# LED_card_GC_REV2.net
KiCad netlist of a schematic drawn in EAGLE
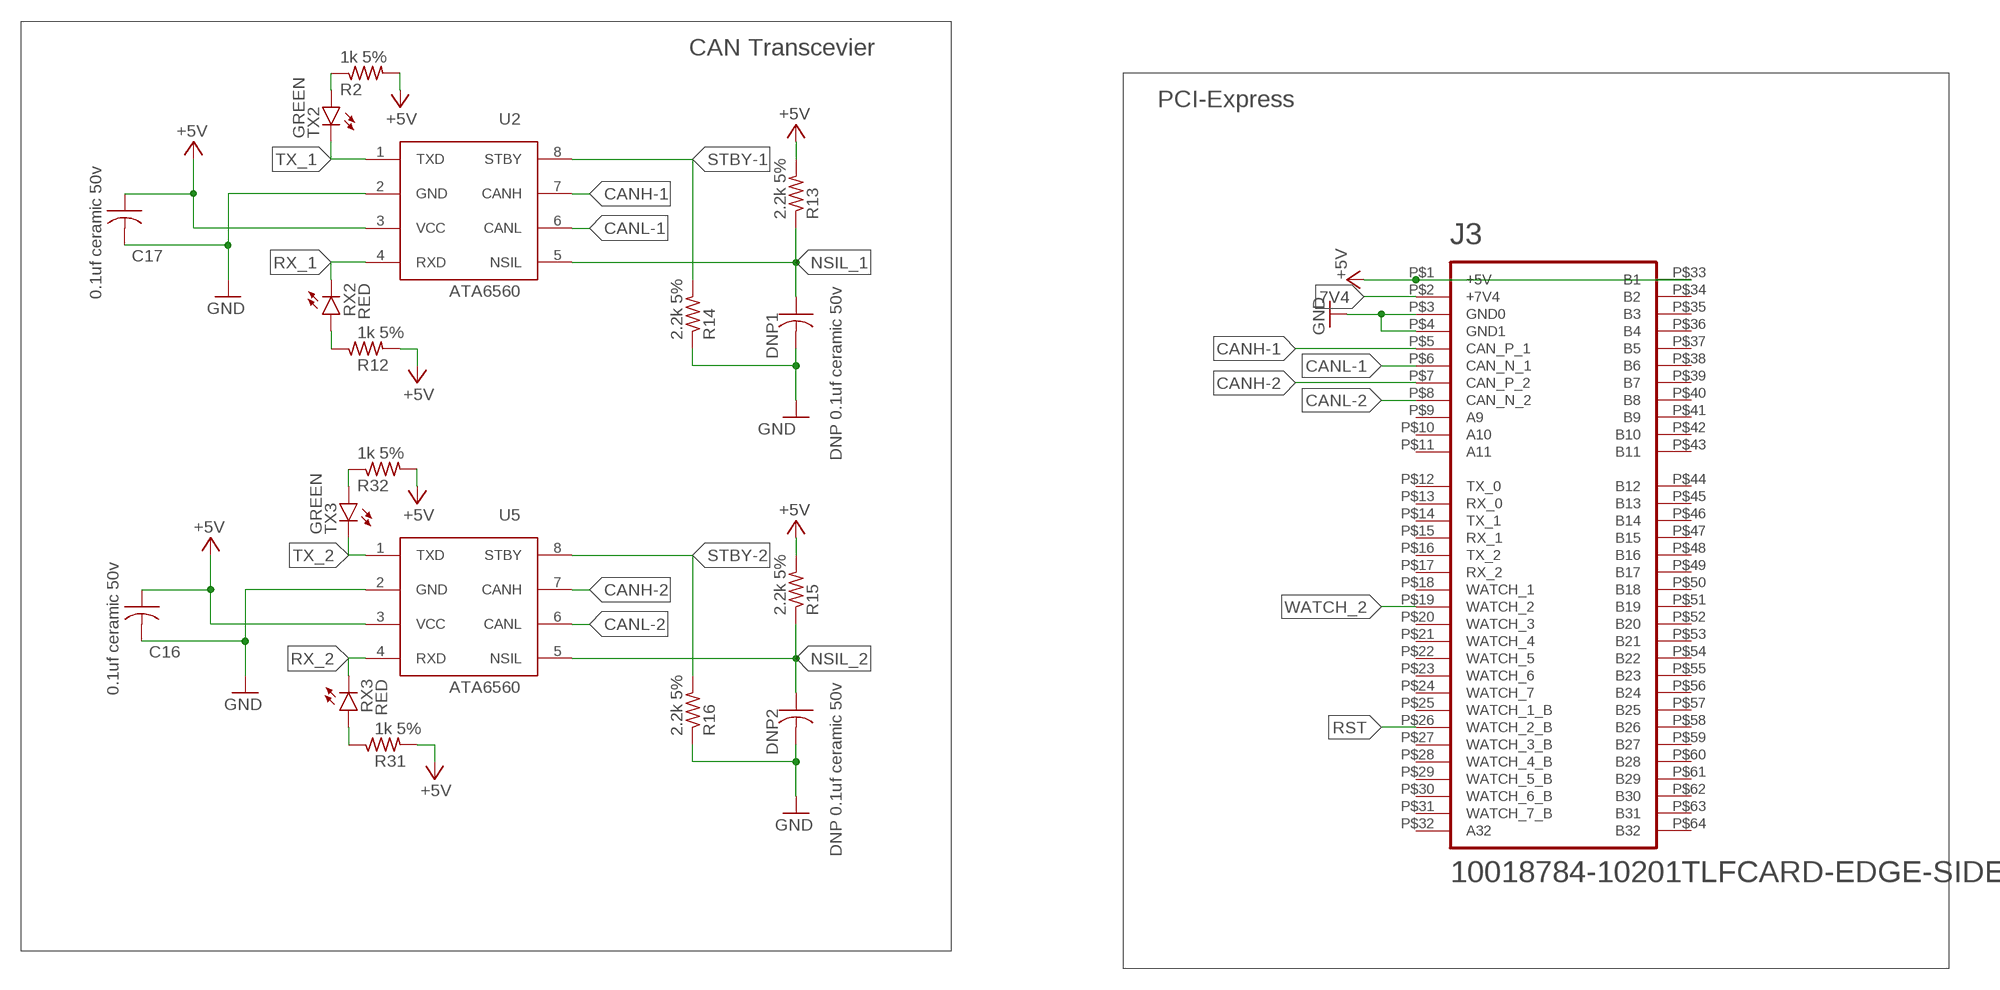
[diagram p0: schematic, sheet 1, part 1 of 3]
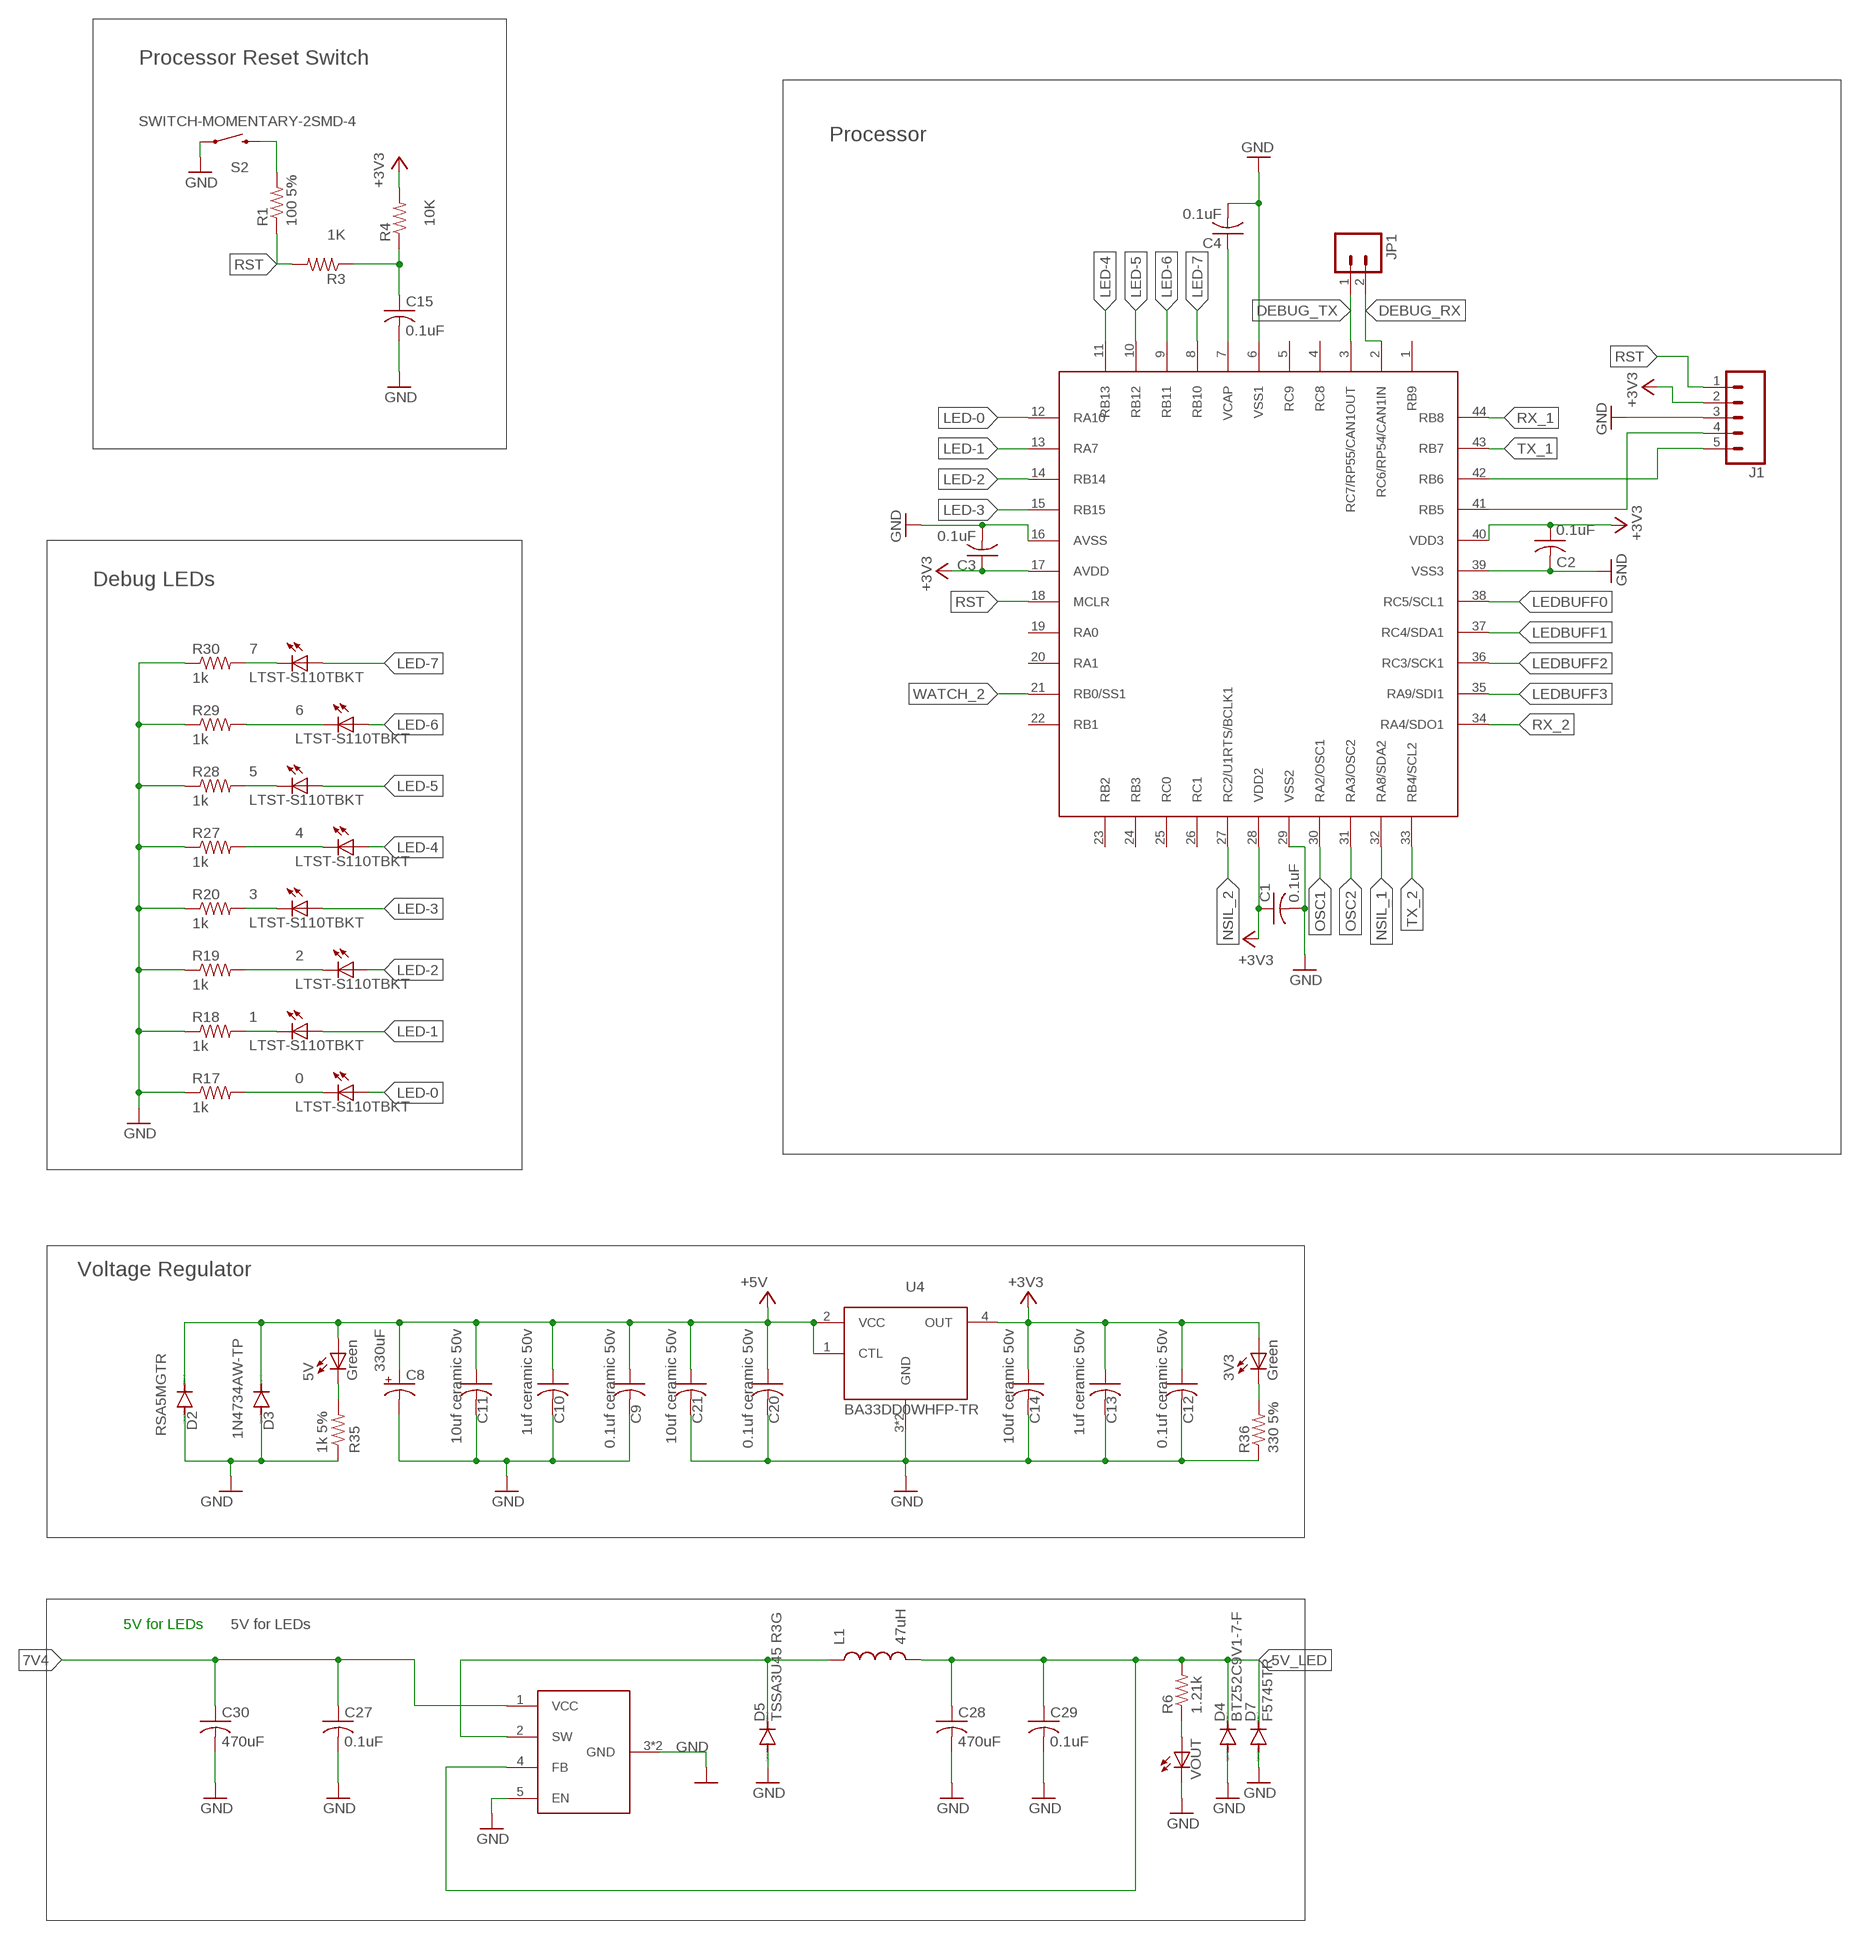
[diagram p1: schematic, sheet 1, part 2 of 3]
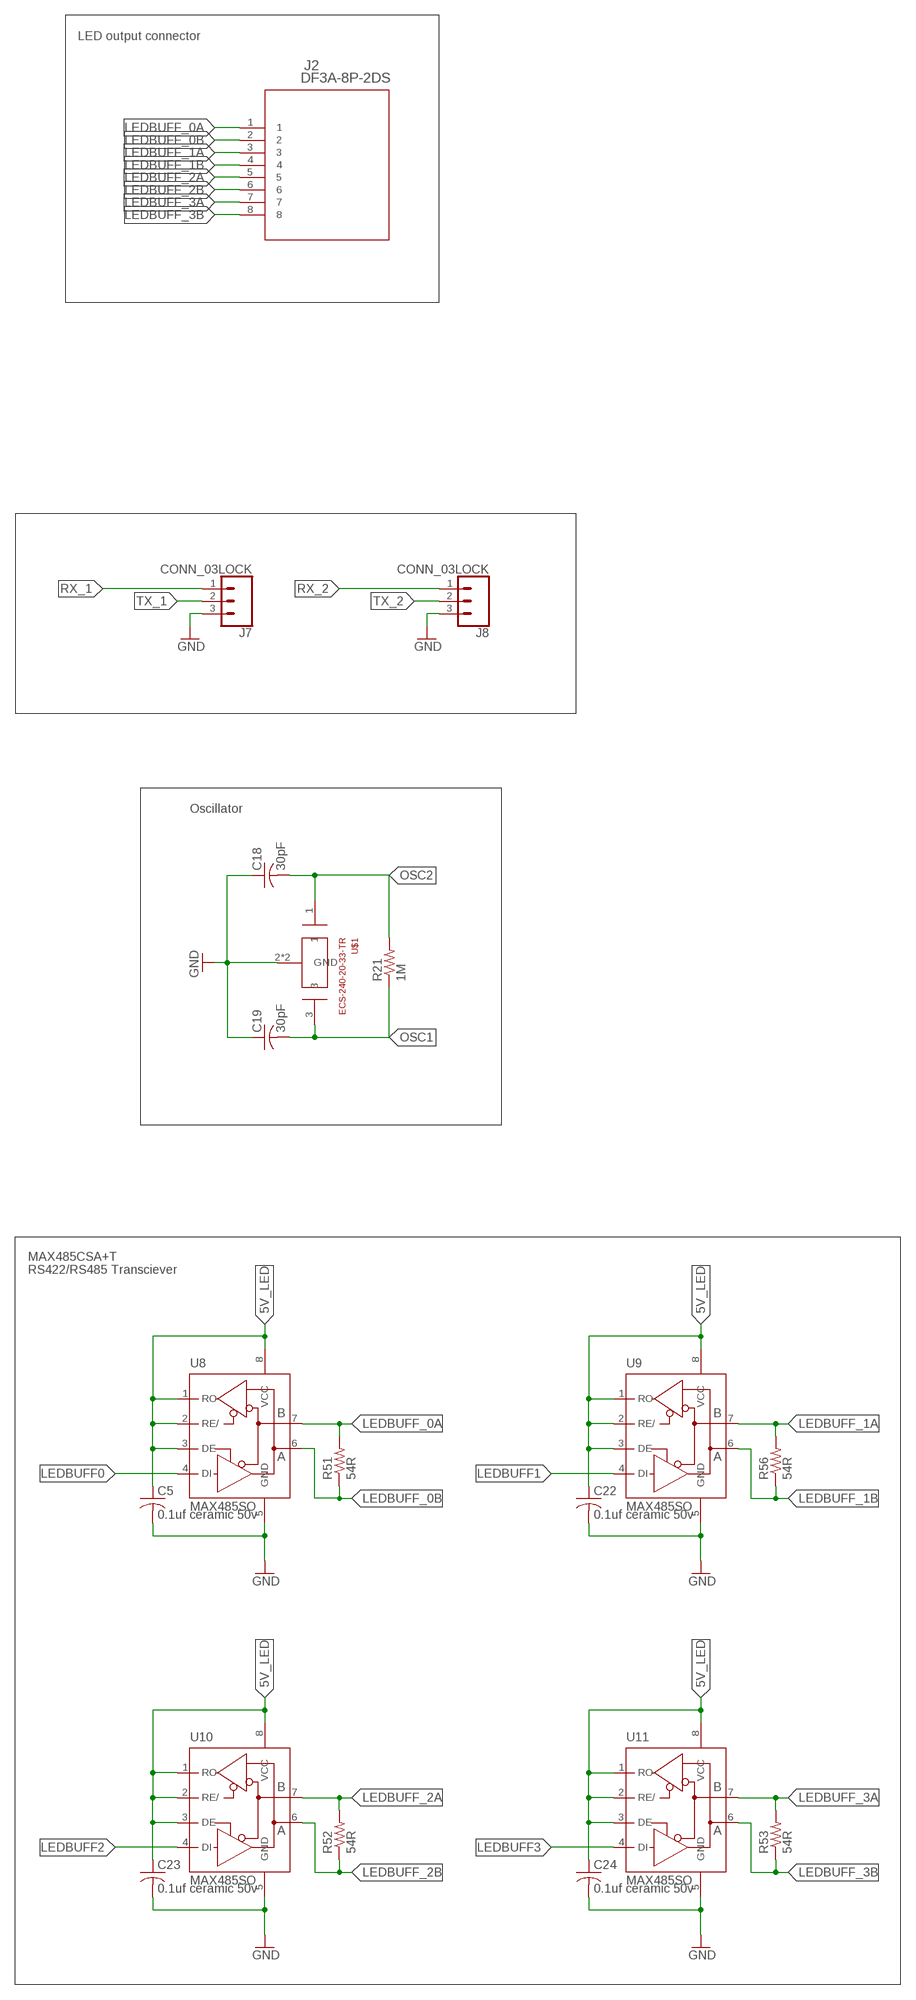
[diagram p2: schematic, sheet 1, part 3 of 3]

(export (version "E")
  (design (tool "Eeschema 10.0.6"))
  (components
    (comp (ref "0")
      (value "LTST-S110TBKT")
      (footprint "eagle-import:LED-90")
      (libsource (lib "eagle-import") (part "LTST-S110TBKT"))
    )
    (comp (ref "1")
      (value "LTST-S110TBKT")
      (footprint "eagle-import:LED-90")
      (libsource (lib "eagle-import") (part "LTST-S110TBKT"))
    )
    (comp (ref "2")
      (value "LTST-S110TBKT")
      (footprint "eagle-import:LED-90")
      (libsource (lib "eagle-import") (part "LTST-S110TBKT"))
    )
    (comp (ref "3")
      (value "LTST-S110TBKT")
      (footprint "eagle-import:LED-90")
      (libsource (lib "eagle-import") (part "LTST-S110TBKT"))
    )
    (comp (ref "3V3")
      (value "Green")
      (footprint "eagle-import:LED-90")
      (libsource (lib "eagle-import") (part "LTST-S110TBKT"))
    )
    (comp (ref "4")
      (value "LTST-S110TBKT")
      (footprint "eagle-import:LED-90")
      (libsource (lib "eagle-import") (part "LTST-S110TBKT"))
    )
    (comp (ref "5")
      (value "LTST-S110TBKT")
      (footprint "eagle-import:LED-90")
      (libsource (lib "eagle-import") (part "LTST-S110TBKT"))
    )
    (comp (ref "5V")
      (value "Green")
      (footprint "eagle-import:LED-90")
      (libsource (lib "eagle-import") (part "LTST-S110TBKT"))
    )
    (comp (ref "6")
      (value "LTST-S110TBKT")
      (footprint "eagle-import:LED-90")
      (libsource (lib "eagle-import") (part "LTST-S110TBKT"))
    )
    (comp (ref "7")
      (value "LTST-S110TBKT")
      (footprint "eagle-import:LED-90")
      (libsource (lib "eagle-import") (part "LTST-S110TBKT"))
    )
    (comp (ref "C1")
      (value "0.1uF")
      (footprint "eagle-import:C0805")
      (libsource (lib "eagle-import") (part "C-US_0805C0805"))
    )
    (comp (ref "C2")
      (value "0.1uF")
      (footprint "eagle-import:C0805")
      (libsource (lib "eagle-import") (part "C-US_0805C0805"))
    )
    (comp (ref "C3")
      (value "0.1uF")
      (footprint "eagle-import:C0805")
      (libsource (lib "eagle-import") (part "C-US_0805C0805"))
    )
    (comp (ref "C4")
      (value "0.1uF")
      (footprint "eagle-import:C0805")
      (libsource (lib "eagle-import") (part "C-US_0805C0805"))
    )
    (comp (ref "C5")
      (value "0.1uf ceramic 50v")
      (footprint "eagle-import:C0805")
      (libsource (lib "eagle-import") (part "rcl_C-USC0805"))
    )
    (comp (ref "C8")
      (value "330uF")
      (footprint "eagle-import:140CLH-1014")
      (libsource (lib "eagle-import") (part "CPOL-US140CLH-1014"))
    )
    (comp (ref "C9")
      (value "0.1uf ceramic 50v")
      (footprint "eagle-import:C0805")
      (libsource (lib "eagle-import") (part "C-US_0805C0805"))
    )
    (comp (ref "C10")
      (value "1uf ceramic 50v")
      (footprint "eagle-import:C0805")
      (libsource (lib "eagle-import") (part "C-US_0805C0805"))
    )
    (comp (ref "C11")
      (value "10uf ceramic 50v")
      (footprint "eagle-import:C0805")
      (libsource (lib "eagle-import") (part "C-US_0805C0805"))
    )
    (comp (ref "C12")
      (value "0.1uf ceramic 50v")
      (footprint "eagle-import:C0805")
      (libsource (lib "eagle-import") (part "C-US_0805C0805"))
    )
    (comp (ref "C13")
      (value "1uf ceramic 50v")
      (footprint "eagle-import:C0805")
      (libsource (lib "eagle-import") (part "C-US_0805C0805"))
    )
    (comp (ref "C14")
      (value "10uf ceramic 50v")
      (footprint "eagle-import:C0805")
      (libsource (lib "eagle-import") (part "C-US_0805C0805"))
    )
    (comp (ref "C15")
      (value "0.1uF")
      (footprint "eagle-import:C0805")
      (libsource (lib "eagle-import") (part "C-US_0805C0805"))
    )
    (comp (ref "C16")
      (value "0.1uf ceramic 50v")
      (footprint "eagle-import:C0805")
      (libsource (lib "eagle-import") (part "C-US_0805C0805"))
    )
    (comp (ref "C17")
      (value "0.1uf ceramic 50v")
      (footprint "eagle-import:C0805")
      (libsource (lib "eagle-import") (part "C-US_0805C0805"))
    )
    (comp (ref "C18")
      (value "30pF")
      (footprint "eagle-import:C0805")
      (libsource (lib "eagle-import") (part "C-US_0805C0805"))
    )
    (comp (ref "C19")
      (value "30pF")
      (footprint "eagle-import:C0805")
      (libsource (lib "eagle-import") (part "C-US_0805C0805"))
    )
    (comp (ref "C20")
      (value "0.1uf ceramic 50v")
      (footprint "eagle-import:C0805")
      (libsource (lib "eagle-import") (part "C-US_0805C0805"))
    )
    (comp (ref "C21")
      (value "10uf ceramic 50v")
      (footprint "eagle-import:C0805")
      (libsource (lib "eagle-import") (part "C-US_0805C0805"))
    )
    (comp (ref "C22")
      (value "0.1uf ceramic 50v")
      (footprint "eagle-import:C0805")
      (libsource (lib "eagle-import") (part "rcl_C-USC0805"))
    )
    (comp (ref "C23")
      (value "0.1uf ceramic 50v")
      (footprint "eagle-import:C0805")
      (libsource (lib "eagle-import") (part "rcl_C-USC0805"))
    )
    (comp (ref "C24")
      (value "0.1uf ceramic 50v")
      (footprint "eagle-import:C0805")
      (libsource (lib "eagle-import") (part "rcl_C-USC0805"))
    )
    (comp (ref "C27")
      (value "0.1uF")
      (footprint "eagle-import:C1825")
      (libsource (lib "eagle-import") (part "C-USC1825"))
    )
    (comp (ref "C28")
      (value "470uF")
      (footprint "eagle-import:C1825")
      (libsource (lib "eagle-import") (part "C-USC1825"))
    )
    (comp (ref "C29")
      (value "0.1uF")
      (footprint "eagle-import:C1825")
      (libsource (lib "eagle-import") (part "C-USC1825"))
    )
    (comp (ref "C30")
      (value "470uF")
      (footprint "eagle-import:C1825")
      (libsource (lib "eagle-import") (part "C-USC1825"))
    )
    (comp (ref "D2")
      (value "RSA5MGTR")
      (footprint "eagle-import:SOD123")
      (libsource (lib "eagle-import") (part "DIODE-SOD123"))
    )
    (comp (ref "D3")
      (value "1N4734AW-TP")
      (footprint "eagle-import:SOD123")
      (fields (field (name "SPICEPREFIX") "D"))
      (libsource (lib "eagle-import") (part "DIODE-SOD123"))
    )
    (comp (ref "D4")
      (value "BTZ52C9V1-7-F")
      (footprint "eagle-import:SOD123")
      (libsource (lib "eagle-import") (part "DIODE-SOD123"))
    )
    (comp (ref "D5")
      (value "TSSA3U45 R3G")
      (footprint "eagle-import:DO214AC")
      (libsource (lib "eagle-import") (part "DIODE-DO214AC"))
    )
    (comp (ref "D7")
      (value "F5745TR")
      (footprint "eagle-import:SOD123")
      (libsource (lib "eagle-import") (part "DIODE-SOD123"))
    )
    (comp (ref "DNP1")
      (value "DNP 0.1uf ceramic 50v")
      (footprint "eagle-import:C0805")
      (libsource (lib "eagle-import") (part "C-US_0805C0805"))
    )
    (comp (ref "DNP2")
      (value "DNP 0.1uf ceramic 50v")
      (footprint "eagle-import:C0805")
      (libsource (lib "eagle-import") (part "C-US_0805C0805"))
    )
    (comp (ref "J1")
      (value "CONN_05LOCK")
      (footprint "eagle-import:1X05_LOCK")
      (libsource (lib "eagle-import") (part "CONN_05LOCK"))
    )
    (comp (ref "J2")
      (value "DF3A-8P-2DS")
      (footprint "eagle-import:CON8_1X8_R_DF3")
      (libsource (lib "eagle-import") (part "DF3A-8P-2DS"))
    )
    (comp (ref "J3")
      (value "10018784-10201TLFCARD-EDGE-SIDE")
      (footprint "eagle-import:CARDEDGE_SIDE")
      (libsource (lib "eagle-import") (part "10018784-10201TLFCARD-EDGE-SIDE"))
    )
    (comp (ref "J7")
      (value "CONN_03LOCK")
      (footprint "eagle-import:1X03_LOCK")
      (libsource (lib "eagle-import") (part "CONN_03LOCK"))
    )
    (comp (ref "J8")
      (value "CONN_03LOCK")
      (footprint "eagle-import:1X03_LOCK")
      (libsource (lib "eagle-import") (part "CONN_03LOCK"))
    )
    (comp (ref "JP1")
      (value "CONN_02PTH")
      (footprint "eagle-import:1X02")
      (libsource (lib "eagle-import") (part "CONN_02PTH"))
    )
    (comp (ref "L1")
      (value "47uH")
      (footprint "eagle-import:0805")
      (libsource (lib "eagle-import") (part "INDUCTOR1"))
    )
    (comp (ref "R1")
      (value "100 5%")
      (footprint "eagle-import:R0805")
      (libsource (lib "eagle-import") (part "R-US_0805R0805"))
    )
    (comp (ref "R2")
      (value "1k 5%")
      (footprint "eagle-import:R0805")
      (libsource (lib "eagle-import") (part "R-US_0805R0805"))
    )
    (comp (ref "R3")
      (value "1K")
      (footprint "eagle-import:R0805")
      (libsource (lib "eagle-import") (part "R-US_0805R0805"))
    )
    (comp (ref "R4")
      (value "10K")
      (footprint "eagle-import:R0805")
      (libsource (lib "eagle-import") (part "R-US_0805R0805"))
    )
    (comp (ref "R6")
      (value "1.21k")
      (footprint "eagle-import:R0805")
      (libsource (lib "eagle-import") (part "R-US_R0805"))
    )
    (comp (ref "R12")
      (value "1k 5%")
      (footprint "eagle-import:R0805")
      (libsource (lib "eagle-import") (part "R-US_0805R0805"))
    )
    (comp (ref "R13")
      (value "2.2k 5%")
      (footprint "eagle-import:R0805")
      (libsource (lib "eagle-import") (part "R-US_0805R0805"))
    )
    (comp (ref "R14")
      (value "2.2k 5%")
      (footprint "eagle-import:R0805")
      (libsource (lib "eagle-import") (part "R-US_0805R0805"))
    )
    (comp (ref "R15")
      (value "2.2k 5%")
      (footprint "eagle-import:R0805")
      (libsource (lib "eagle-import") (part "R-US_0805R0805"))
    )
    (comp (ref "R16")
      (value "2.2k 5%")
      (footprint "eagle-import:R0805")
      (libsource (lib "eagle-import") (part "R-US_0805R0805"))
    )
    (comp (ref "R17")
      (value "1k")
      (footprint "eagle-import:R0805")
      (libsource (lib "eagle-import") (part "R-US_0805R0805"))
    )
    (comp (ref "R18")
      (value "1k")
      (footprint "eagle-import:R0805")
      (libsource (lib "eagle-import") (part "R-US_0805R0805"))
    )
    (comp (ref "R19")
      (value "1k")
      (footprint "eagle-import:R0805")
      (libsource (lib "eagle-import") (part "R-US_0805R0805"))
    )
    (comp (ref "R20")
      (value "1k")
      (footprint "eagle-import:R0805")
      (libsource (lib "eagle-import") (part "R-US_0805R0805"))
    )
    (comp (ref "R21")
      (value "1M")
      (footprint "eagle-import:R0805")
      (libsource (lib "eagle-import") (part "R-US_0805R0805"))
    )
    (comp (ref "R27")
      (value "1k")
      (footprint "eagle-import:R0805")
      (libsource (lib "eagle-import") (part "R-US_0805R0805"))
    )
    (comp (ref "R28")
      (value "1k")
      (footprint "eagle-import:R0805")
      (libsource (lib "eagle-import") (part "R-US_0805R0805"))
    )
    (comp (ref "R29")
      (value "1k")
      (footprint "eagle-import:R0805")
      (libsource (lib "eagle-import") (part "R-US_0805R0805"))
    )
    (comp (ref "R30")
      (value "1k")
      (footprint "eagle-import:R0805")
      (libsource (lib "eagle-import") (part "R-US_0805R0805"))
    )
    (comp (ref "R31")
      (value "1k 5%")
      (footprint "eagle-import:R0805")
      (libsource (lib "eagle-import") (part "R-US_0805R0805"))
    )
    (comp (ref "R32")
      (value "1k 5%")
      (footprint "eagle-import:R0805")
      (libsource (lib "eagle-import") (part "R-US_0805R0805"))
    )
    (comp (ref "R35")
      (value "1k 5%")
      (footprint "eagle-import:R0805")
      (libsource (lib "eagle-import") (part "R-US_0805R0805"))
    )
    (comp (ref "R36")
      (value "330 5%")
      (footprint "eagle-import:R0805")
      (libsource (lib "eagle-import") (part "R-US_0805R0805"))
    )
    (comp (ref "R51")
      (value "54R")
      (footprint "eagle-import:0805")
      (libsource (lib "eagle-import") (part "RESISTOR0805-RES"))
    )
    (comp (ref "R52")
      (value "54R")
      (footprint "eagle-import:0805")
      (libsource (lib "eagle-import") (part "RESISTOR0805-RES"))
    )
    (comp (ref "R53")
      (value "54R")
      (footprint "eagle-import:0805")
      (libsource (lib "eagle-import") (part "RESISTOR0805-RES"))
    )
    (comp (ref "R56")
      (value "54R")
      (footprint "eagle-import:0805")
      (libsource (lib "eagle-import") (part "RESISTOR0805-RES"))
    )
    (comp (ref "RX2")
      (value "RED")
      (footprint "eagle-import:CHIP-LED0805")
      (libsource (lib "eagle-import") (part "LEDS_0805CHIP-LED0805"))
    )
    (comp (ref "RX3")
      (value "RED")
      (footprint "eagle-import:CHIP-LED0805")
      (libsource (lib "eagle-import") (part "LEDS_0805CHIP-LED0805"))
    )
    (comp (ref "S2")
      (value "SWITCH-MOMENTARY-2SMD-4")
      (footprint "eagle-import:TACTILE_SWITCH_TALL")
      (fields (field (name "POPULARITY") "100"))
      (libsource (lib "eagle-import") (part "SWITCH-MOMENTARY-2SMD-4"))
    )
    (comp (ref "TX2")
      (value "GREEN")
      (footprint "eagle-import:CHIP-LED0805")
      (libsource (lib "eagle-import") (part "LEDS_0805CHIP-LED0805"))
    )
    (comp (ref "TX3")
      (value "GREEN")
      (footprint "eagle-import:CHIP-LED0805")
      (libsource (lib "eagle-import") (part "LEDS_0805CHIP-LED0805"))
    )
    (comp (ref "U$1")
      (value "ECS-240-20-33-TR")
      (footprint "eagle-import:ECX-32")
      (libsource (lib "eagle-import") (part "ECS-240-20-33-TR"))
    )
    (comp (ref "U$3")
      (value "TS2596CM550")
      (footprint "eagle-import:HRP5")
      (libsource (lib "eagle-import") (part "TS2596CM550"))
    )
    (comp (ref "U2")
      (value "ATA6560")
      (footprint "eagle-import:SO08")
      (libsource (lib "eagle-import") (part "ATA6560"))
    )
    (comp (ref "U3")
      (value "DSPIC33EP512GM604")
      (footprint "eagle-import:TQFP-44")
      (libsource (lib "eagle-import") (part "DSPIC33EP512GM604"))
    )
    (comp (ref "U4")
      (value "BA33DD0WHFP-TR")
      (footprint "eagle-import:HRP5")
      (libsource (lib "eagle-import") (part "BA33DD0WHFP-TR"))
    )
    (comp (ref "U5")
      (value "ATA6560")
      (footprint "eagle-import:SO08")
      (libsource (lib "eagle-import") (part "ATA6560"))
    )
    (comp (ref "U8")
      (value "MAX485SO")
      (footprint "eagle-import:SO08")
      (libsource (lib "eagle-import") (part "MAX485SO"))
    )
    (comp (ref "U9")
      (value "MAX485SO")
      (footprint "eagle-import:SO08")
      (libsource (lib "eagle-import") (part "MAX485SO"))
    )
    (comp (ref "U10")
      (value "MAX485SO")
      (footprint "eagle-import:SO08")
      (libsource (lib "eagle-import") (part "MAX485SO"))
    )
    (comp (ref "U11")
      (value "MAX485SO")
      (footprint "eagle-import:SO08")
      (libsource (lib "eagle-import") (part "MAX485SO"))
    )
    (comp (ref "VOUT1")
      (value "VOUT")
      (footprint "eagle-import:CHIP-LED0805")
      (libsource (lib "eagle-import") (part "LEDCHIP-LED0805"))
    )
  )
  (nets
    (net (code "1") (name "+3V3") (class "Default")
      (node (ref "3V3") (pin "+") (pinfunction "A+_+") (pintype "passive"))
      (node (ref "C1") (pin "1") (pinfunction "1_1") (pintype "passive"))
      (node (ref "C12") (pin "1") (pinfunction "1_1") (pintype "passive"))
      (node (ref "C13") (pin "1") (pinfunction "1_1") (pintype "passive"))
      (node (ref "C14") (pin "1") (pinfunction "1_1") (pintype "passive"))
      (node (ref "C2") (pin "1") (pinfunction "1_1") (pintype "passive"))
      (node (ref "C3") (pin "1") (pinfunction "1_1") (pintype "passive"))
      (node (ref "J1") (pin "2") (pinfunction "2_2") (pintype "passive"))
      (node (ref "R4") (pin "2") (pinfunction "2_2") (pintype "passive"))
      (node (ref "U3") (pin "17") (pinfunction "AVDD_17") (pintype "power_in"))
      (node (ref "U3") (pin "28") (pinfunction "VDD2_28") (pintype "power_in"))
      (node (ref "U3") (pin "40") (pinfunction "VDD3_40") (pintype "power_in"))
      (node (ref "U4") (pin "4") (pinfunction "OUT_4") (pintype "bidirectional"))
    )
    (net (code "2") (name "+5V") (class "Default")
      (node (ref "5V") (pin "+") (pinfunction "A+_+") (pintype "passive"))
      (node (ref "C10") (pin "1") (pinfunction "1_1") (pintype "passive"))
      (node (ref "C11") (pin "1") (pinfunction "1_1") (pintype "passive"))
      (node (ref "C16") (pin "1") (pinfunction "1_1") (pintype "passive"))
      (node (ref "C17") (pin "1") (pinfunction "1_1") (pintype "passive"))
      (node (ref "C20") (pin "1") (pinfunction "1_1") (pintype "passive"))
      (node (ref "C21") (pin "1") (pinfunction "1_1") (pintype "passive"))
      (node (ref "C8") (pin "+") (pinfunction "+_+") (pintype "passive"))
      (node (ref "C9") (pin "1") (pinfunction "1_1") (pintype "passive"))
      (node (ref "D2") (pin "C") (pinfunction "C_C") (pintype "passive"))
      (node (ref "D3") (pin "C") (pinfunction "C_C") (pintype "passive"))
      (node (ref "J3") (pin "P$1") (pinfunction "+5V_P$1") (pintype "passive"))
      (node (ref "J3") (pin "P$33") (pinfunction "B1_P$33") (pintype "passive"))
      (node (ref "R12") (pin "2") (pinfunction "2_2") (pintype "passive"))
      (node (ref "R13") (pin "2") (pinfunction "2_2") (pintype "passive"))
      (node (ref "R15") (pin "2") (pinfunction "2_2") (pintype "passive"))
      (node (ref "R2") (pin "2") (pinfunction "2_2") (pintype "passive"))
      (node (ref "R31") (pin "2") (pinfunction "2_2") (pintype "passive"))
      (node (ref "R32") (pin "2") (pinfunction "2_2") (pintype "passive"))
      (node (ref "U2") (pin "3") (pinfunction "VCC_3") (pintype "bidirectional"))
      (node (ref "U4") (pin "1") (pinfunction "CTL_1") (pintype "bidirectional"))
      (node (ref "U4") (pin "2") (pinfunction "VCC_2") (pintype "bidirectional"))
      (node (ref "U5") (pin "3") (pinfunction "VCC_3") (pintype "bidirectional"))
    )
    (net (code "3") (name "5V_LED") (class "Default")
      (node (ref "C22") (pin "1") (pinfunction "1_1") (pintype "passive"))
      (node (ref "C23") (pin "1") (pinfunction "1_1") (pintype "passive"))
      (node (ref "C24") (pin "1") (pinfunction "1_1") (pintype "passive"))
      (node (ref "C28") (pin "1") (pinfunction "1_1") (pintype "passive"))
      (node (ref "C29") (pin "1") (pinfunction "1_1") (pintype "passive"))
      (node (ref "C5") (pin "1") (pinfunction "1_1") (pintype "passive"))
      (node (ref "D4") (pin "C") (pinfunction "C_C") (pintype "passive"))
      (node (ref "D7") (pin "C") (pinfunction "C_C") (pintype "passive"))
      (node (ref "L1") (pin "2") (pinfunction "2_2") (pintype "passive"))
      (node (ref "R6") (pin "2") (pinfunction "2_2") (pintype "passive"))
      (node (ref "U$3") (pin "4") (pinfunction "FB_4") (pintype "bidirectional"))
      (node (ref "U10") (pin "1") (pinfunction "RO_1") (pintype "output"))
      (node (ref "U10") (pin "2") (pinfunction "RE/_2") (pintype "input"))
      (node (ref "U10") (pin "3") (pinfunction "DE_3") (pintype "input"))
      (node (ref "U10") (pin "8") (pinfunction "VCC_8") (pintype "bidirectional"))
      (node (ref "U11") (pin "1") (pinfunction "RO_1") (pintype "output"))
      (node (ref "U11") (pin "2") (pinfunction "RE/_2") (pintype "input"))
      (node (ref "U11") (pin "3") (pinfunction "DE_3") (pintype "input"))
      (node (ref "U11") (pin "8") (pinfunction "VCC_8") (pintype "bidirectional"))
      (node (ref "U8") (pin "1") (pinfunction "RO_1") (pintype "output"))
      (node (ref "U8") (pin "2") (pinfunction "RE/_2") (pintype "input"))
      (node (ref "U8") (pin "3") (pinfunction "DE_3") (pintype "input"))
      (node (ref "U8") (pin "8") (pinfunction "VCC_8") (pintype "bidirectional"))
      (node (ref "U9") (pin "1") (pinfunction "RO_1") (pintype "output"))
      (node (ref "U9") (pin "2") (pinfunction "RE/_2") (pintype "input"))
      (node (ref "U9") (pin "3") (pinfunction "DE_3") (pintype "input"))
      (node (ref "U9") (pin "8") (pinfunction "VCC_8") (pintype "bidirectional"))
    )
    (net (code "4") (name "7V4") (class "Default")
      (node (ref "C27") (pin "1") (pinfunction "1_1") (pintype "passive"))
      (node (ref "C30") (pin "1") (pinfunction "1_1") (pintype "passive"))
      (node (ref "J3") (pin "P$2") (pinfunction "+7V4_P$2") (pintype "passive"))
      (node (ref "U$3") (pin "1") (pinfunction "VCC_1") (pintype "bidirectional"))
    )
    (net (code "5") (name "CANH-1") (class "Default")
      (node (ref "J3") (pin "P$5") (pinfunction "CAN_P_1_P$5") (pintype "passive"))
      (node (ref "U2") (pin "7") (pinfunction "CANH_7") (pintype "bidirectional"))
    )
    (net (code "6") (name "CANH-2") (class "Default")
      (node (ref "J3") (pin "P$7") (pinfunction "CAN_P_2_P$7") (pintype "passive"))
      (node (ref "U5") (pin "7") (pinfunction "CANH_7") (pintype "bidirectional"))
    )
    (net (code "7") (name "CANL-1") (class "Default")
      (node (ref "J3") (pin "P$6") (pinfunction "CAN_N_1_P$6") (pintype "passive"))
      (node (ref "U2") (pin "6") (pinfunction "CANL_6") (pintype "bidirectional"))
    )
    (net (code "8") (name "CANL-2") (class "Default")
      (node (ref "J3") (pin "P$8") (pinfunction "CAN_N_2_P$8") (pintype "passive"))
      (node (ref "U5") (pin "6") (pinfunction "CANL_6") (pintype "bidirectional"))
    )
    (net (code "9") (name "DEBUG_RX") (class "Default")
      (node (ref "JP1") (pin "2") (pinfunction "2_2") (pintype "passive"))
      (node (ref "U3") (pin "2") (pinfunction "RC6/RP54/CAN1IN_2") (pintype "bidirectional"))
    )
    (net (code "10") (name "DEBUG_TX") (class "Default")
      (node (ref "JP1") (pin "1") (pinfunction "1_1") (pintype "passive"))
      (node (ref "U3") (pin "3") (pinfunction "RC7/RP55/CAN1OUT_3") (pintype "bidirectional"))
    )
    (net (code "11") (name "GND") (class "Default")
      (node (ref "C1") (pin "2") (pinfunction "2_2") (pintype "passive"))
      (node (ref "C10") (pin "2") (pinfunction "2_2") (pintype "passive"))
      (node (ref "C11") (pin "2") (pinfunction "2_2") (pintype "passive"))
      (node (ref "C12") (pin "2") (pinfunction "2_2") (pintype "passive"))
      (node (ref "C13") (pin "2") (pinfunction "2_2") (pintype "passive"))
      (node (ref "C14") (pin "2") (pinfunction "2_2") (pintype "passive"))
      (node (ref "C15") (pin "2") (pinfunction "2_2") (pintype "passive"))
      (node (ref "C16") (pin "2") (pinfunction "2_2") (pintype "passive"))
      (node (ref "C17") (pin "2") (pinfunction "2_2") (pintype "passive"))
      (node (ref "C18") (pin "1") (pinfunction "1_1") (pintype "passive"))
      (node (ref "C19") (pin "1") (pinfunction "1_1") (pintype "passive"))
      (node (ref "C2") (pin "2") (pinfunction "2_2") (pintype "passive"))
      (node (ref "C20") (pin "2") (pinfunction "2_2") (pintype "passive"))
      (node (ref "C21") (pin "2") (pinfunction "2_2") (pintype "passive"))
      (node (ref "C22") (pin "2") (pinfunction "2_2") (pintype "passive"))
      (node (ref "C23") (pin "2") (pinfunction "2_2") (pintype "passive"))
      (node (ref "C24") (pin "2") (pinfunction "2_2") (pintype "passive"))
      (node (ref "C27") (pin "2") (pinfunction "2_2") (pintype "passive"))
      (node (ref "C28") (pin "2") (pinfunction "2_2") (pintype "passive"))
      (node (ref "C29") (pin "2") (pinfunction "2_2") (pintype "passive"))
      (node (ref "C3") (pin "2") (pinfunction "2_2") (pintype "passive"))
      (node (ref "C30") (pin "2") (pinfunction "2_2") (pintype "passive"))
      (node (ref "C4") (pin "2") (pinfunction "2_2") (pintype "passive"))
      (node (ref "C5") (pin "2") (pinfunction "2_2") (pintype "passive"))
      (node (ref "C8") (pin "-") (pinfunction "-_-") (pintype "passive"))
      (node (ref "C9") (pin "2") (pinfunction "2_2") (pintype "passive"))
      (node (ref "D2") (pin "A") (pinfunction "A_A") (pintype "passive"))
      (node (ref "D3") (pin "A") (pinfunction "A_A") (pintype "passive"))
      (node (ref "D4") (pin "A") (pinfunction "A_A") (pintype "passive"))
      (node (ref "D5") (pin "A") (pinfunction "A_A") (pintype "passive"))
      (node (ref "D7") (pin "A") (pinfunction "A_A") (pintype "passive"))
      (node (ref "DNP1") (pin "2") (pinfunction "2_2") (pintype "passive"))
      (node (ref "DNP2") (pin "2") (pinfunction "2_2") (pintype "passive"))
      (node (ref "J1") (pin "3") (pinfunction "3_3") (pintype "passive"))
      (node (ref "J3") (pin "P$3") (pinfunction "GND0_P$3") (pintype "passive"))
      (node (ref "J3") (pin "P$4") (pinfunction "GND1_P$4") (pintype "passive"))
      (node (ref "J7") (pin "3") (pinfunction "3_3") (pintype "passive"))
      (node (ref "J8") (pin "3") (pinfunction "3_3") (pintype "passive"))
      (node (ref "R14") (pin "1") (pinfunction "1_1") (pintype "passive"))
      (node (ref "R16") (pin "1") (pinfunction "1_1") (pintype "passive"))
      (node (ref "R17") (pin "1") (pinfunction "1_1") (pintype "passive"))
      (node (ref "R18") (pin "1") (pinfunction "1_1") (pintype "passive"))
      (node (ref "R19") (pin "1") (pinfunction "1_1") (pintype "passive"))
      (node (ref "R20") (pin "1") (pinfunction "1_1") (pintype "passive"))
      (node (ref "R27") (pin "1") (pinfunction "1_1") (pintype "passive"))
      (node (ref "R28") (pin "1") (pinfunction "1_1") (pintype "passive"))
      (node (ref "R29") (pin "1") (pinfunction "1_1") (pintype "passive"))
      (node (ref "R30") (pin "1") (pinfunction "1_1") (pintype "passive"))
      (node (ref "R35") (pin "1") (pinfunction "1_1") (pintype "passive"))
      (node (ref "R36") (pin "1") (pinfunction "1_1") (pintype "passive"))
      (node (ref "S2") (pin "A2") (pinfunction "1_A2") (pintype "passive"))
      (node (ref "U$1") (pin "2") (pinfunction "GND_2") (pintype "bidirectional"))
      (node (ref "U$1") (pin "4") (pinfunction "GND_4") (pintype "bidirectional"))
      (node (ref "U$3") (pin "3") (pinfunction "GND_3") (pintype "bidirectional"))
      (node (ref "U$3") (pin "5") (pinfunction "EN_5") (pintype "bidirectional"))
      (node (ref "U$3") (pin "G") (pinfunction "GND_G") (pintype "bidirectional"))
      (node (ref "U10") (pin "5") (pinfunction "GND_5") (pintype "bidirectional"))
      (node (ref "U11") (pin "5") (pinfunction "GND_5") (pintype "bidirectional"))
      (node (ref "U2") (pin "2") (pinfunction "GND_2") (pintype "bidirectional"))
      (node (ref "U3") (pin "16") (pinfunction "AVSS_16") (pintype "power_in"))
      (node (ref "U3") (pin "29") (pinfunction "VSS2_29") (pintype "power_in"))
      (node (ref "U3") (pin "39") (pinfunction "VSS3_39") (pintype "power_in"))
      (node (ref "U3") (pin "6") (pinfunction "VSS1_6") (pintype "power_in"))
      (node (ref "U4") (pin "3") (pinfunction "GND_3") (pintype "bidirectional"))
      (node (ref "U4") (pin "G") (pinfunction "GND_G") (pintype "bidirectional"))
      (node (ref "U5") (pin "2") (pinfunction "GND_2") (pintype "bidirectional"))
      (node (ref "U8") (pin "5") (pinfunction "GND_5") (pintype "bidirectional"))
      (node (ref "U9") (pin "5") (pinfunction "GND_5") (pintype "bidirectional"))
      (node (ref "VOUT1") (pin "C") (pinfunction "C_C") (pintype "passive"))
    )
    (net (code "12") (name "LED-0") (class "Default")
      (node (ref "0") (pin "+") (pinfunction "A+_+") (pintype "passive"))
      (node (ref "U3") (pin "12") (pinfunction "RA10_12") (pintype "bidirectional"))
    )
    (net (code "13") (name "LED-1") (class "Default")
      (node (ref "1") (pin "+") (pinfunction "A+_+") (pintype "passive"))
      (node (ref "U3") (pin "13") (pinfunction "RA7_13") (pintype "bidirectional"))
    )
    (net (code "14") (name "LED-2") (class "Default")
      (node (ref "2") (pin "+") (pinfunction "A+_+") (pintype "passive"))
      (node (ref "U3") (pin "14") (pinfunction "RB14_14") (pintype "bidirectional"))
    )
    (net (code "15") (name "LED-3") (class "Default")
      (node (ref "3") (pin "+") (pinfunction "A+_+") (pintype "passive"))
      (node (ref "U3") (pin "15") (pinfunction "RB15_15") (pintype "bidirectional"))
    )
    (net (code "16") (name "LED-4") (class "Default")
      (node (ref "4") (pin "+") (pinfunction "A+_+") (pintype "passive"))
      (node (ref "U3") (pin "11") (pinfunction "RB13_11") (pintype "bidirectional"))
    )
    (net (code "17") (name "LED-5") (class "Default")
      (node (ref "5") (pin "+") (pinfunction "A+_+") (pintype "passive"))
      (node (ref "U3") (pin "10") (pinfunction "RB12_10") (pintype "bidirectional"))
    )
    (net (code "18") (name "LED-6") (class "Default")
      (node (ref "6") (pin "+") (pinfunction "A+_+") (pintype "passive"))
      (node (ref "U3") (pin "9") (pinfunction "RB11_9") (pintype "bidirectional"))
    )
    (net (code "19") (name "LED-7") (class "Default")
      (node (ref "7") (pin "+") (pinfunction "A+_+") (pintype "passive"))
      (node (ref "U3") (pin "8") (pinfunction "RB10_8") (pintype "bidirectional"))
    )
    (net (code "20") (name "LEDBUFF0") (class "Default")
      (node (ref "U3") (pin "38") (pinfunction "RC5/SCL1_38") (pintype "bidirectional"))
      (node (ref "U8") (pin "4") (pinfunction "DI_4") (pintype "input"))
    )
    (net (code "21") (name "LEDBUFF1") (class "Default")
      (node (ref "U3") (pin "37") (pinfunction "RC4/SDA1_37") (pintype "bidirectional"))
      (node (ref "U9") (pin "4") (pinfunction "DI_4") (pintype "input"))
    )
    (net (code "22") (name "LEDBUFF2") (class "Default")
      (node (ref "U10") (pin "4") (pinfunction "DI_4") (pintype "input"))
      (node (ref "U3") (pin "36") (pinfunction "RC3/SCK1_36") (pintype "bidirectional"))
    )
    (net (code "23") (name "LEDBUFF3") (class "Default")
      (node (ref "U11") (pin "4") (pinfunction "DI_4") (pintype "input"))
      (node (ref "U3") (pin "35") (pinfunction "RA9/SDI1_35") (pintype "bidirectional"))
    )
    (net (code "24") (name "LEDBUFF_0A") (class "Default")
      (node (ref "J2") (pin "1") (pinfunction "1_1") (pintype "passive"))
      (node (ref "R51") (pin "2") (pinfunction "2_2") (pintype "passive"))
      (node (ref "U8") (pin "7") (pinfunction "B_7") (pintype "passive"))
    )
    (net (code "25") (name "LEDBUFF_0B") (class "Default")
      (node (ref "J2") (pin "2") (pinfunction "2_2") (pintype "passive"))
      (node (ref "R51") (pin "1") (pinfunction "1_1") (pintype "passive"))
      (node (ref "U8") (pin "6") (pinfunction "A_6") (pintype "passive"))
    )
    (net (code "26") (name "LEDBUFF_1A") (class "Default")
      (node (ref "J2") (pin "3") (pinfunction "3_3") (pintype "passive"))
      (node (ref "R56") (pin "2") (pinfunction "2_2") (pintype "passive"))
      (node (ref "U9") (pin "7") (pinfunction "B_7") (pintype "passive"))
    )
    (net (code "27") (name "LEDBUFF_1B") (class "Default")
      (node (ref "J2") (pin "4") (pinfunction "4_4") (pintype "passive"))
      (node (ref "R56") (pin "1") (pinfunction "1_1") (pintype "passive"))
      (node (ref "U9") (pin "6") (pinfunction "A_6") (pintype "passive"))
    )
    (net (code "28") (name "LEDBUFF_2A") (class "Default")
      (node (ref "J2") (pin "5") (pinfunction "5_5") (pintype "passive"))
      (node (ref "R52") (pin "2") (pinfunction "2_2") (pintype "passive"))
      (node (ref "U10") (pin "7") (pinfunction "B_7") (pintype "passive"))
    )
    (net (code "29") (name "LEDBUFF_2B") (class "Default")
      (node (ref "J2") (pin "6") (pinfunction "6_6") (pintype "passive"))
      (node (ref "R52") (pin "1") (pinfunction "1_1") (pintype "passive"))
      (node (ref "U10") (pin "6") (pinfunction "A_6") (pintype "passive"))
    )
    (net (code "30") (name "LEDBUFF_3A") (class "Default")
      (node (ref "J2") (pin "7") (pinfunction "7_7") (pintype "passive"))
      (node (ref "R53") (pin "2") (pinfunction "2_2") (pintype "passive"))
      (node (ref "U11") (pin "7") (pinfunction "B_7") (pintype "passive"))
    )
    (net (code "31") (name "LEDBUFF_3B") (class "Default")
      (node (ref "J2") (pin "8") (pinfunction "8_8") (pintype "passive"))
      (node (ref "R53") (pin "1") (pinfunction "1_1") (pintype "passive"))
      (node (ref "U11") (pin "6") (pinfunction "A_6") (pintype "passive"))
    )
    (net (code "32") (name "NSIL_1") (class "Default")
      (node (ref "DNP1") (pin "1") (pinfunction "1_1") (pintype "passive"))
      (node (ref "R13") (pin "1") (pinfunction "1_1") (pintype "passive"))
      (node (ref "U2") (pin "5") (pinfunction "NSIL_5") (pintype "bidirectional"))
      (node (ref "U3") (pin "32") (pinfunction "RA8/SDA2_32") (pintype "bidirectional"))
    )
    (net (code "33") (name "NSIL_2") (class "Default")
      (node (ref "DNP2") (pin "1") (pinfunction "1_1") (pintype "passive"))
      (node (ref "R15") (pin "1") (pinfunction "1_1") (pintype "passive"))
      (node (ref "U3") (pin "27") (pinfunction "RC2/U1RTS/BCLK1_27") (pintype "bidirectional"))
      (node (ref "U5") (pin "5") (pinfunction "NSIL_5") (pintype "bidirectional"))
    )
    (net (code "34") (name "Net-(0-C-)") (class "Default")
      (node (ref "0") (pin "-") (pinfunction "C-_-") (pintype "passive"))
      (node (ref "R17") (pin "2") (pinfunction "2_2") (pintype "passive"))
    )
    (net (code "35") (name "Net-(1-C-)") (class "Default")
      (node (ref "1") (pin "-") (pinfunction "C-_-") (pintype "passive"))
      (node (ref "R18") (pin "2") (pinfunction "2_2") (pintype "passive"))
    )
    (net (code "36") (name "Net-(2-C-)") (class "Default")
      (node (ref "2") (pin "-") (pinfunction "C-_-") (pintype "passive"))
      (node (ref "R19") (pin "2") (pinfunction "2_2") (pintype "passive"))
    )
    (net (code "37") (name "Net-(3-C-)") (class "Default")
      (node (ref "3") (pin "-") (pinfunction "C-_-") (pintype "passive"))
      (node (ref "R20") (pin "2") (pinfunction "2_2") (pintype "passive"))
    )
    (net (code "38") (name "Net-(3V3-C-)") (class "Default")
      (node (ref "3V3") (pin "-") (pinfunction "C-_-") (pintype "passive"))
      (node (ref "R36") (pin "2") (pinfunction "2_2") (pintype "passive"))
    )
    (net (code "39") (name "Net-(4-C-)") (class "Default")
      (node (ref "4") (pin "-") (pinfunction "C-_-") (pintype "passive"))
      (node (ref "R27") (pin "2") (pinfunction "2_2") (pintype "passive"))
    )
    (net (code "40") (name "Net-(5-C-)") (class "Default")
      (node (ref "5") (pin "-") (pinfunction "C-_-") (pintype "passive"))
      (node (ref "R28") (pin "2") (pinfunction "2_2") (pintype "passive"))
    )
    (net (code "41") (name "Net-(5V-C-)") (class "Default")
      (node (ref "5V") (pin "-") (pinfunction "C-_-") (pintype "passive"))
      (node (ref "R35") (pin "2") (pinfunction "2_2") (pintype "passive"))
    )
    (net (code "42") (name "Net-(6-C-)") (class "Default")
      (node (ref "6") (pin "-") (pinfunction "C-_-") (pintype "passive"))
      (node (ref "R29") (pin "2") (pinfunction "2_2") (pintype "passive"))
    )
    (net (code "43") (name "Net-(7-C-)") (class "Default")
      (node (ref "7") (pin "-") (pinfunction "C-_-") (pintype "passive"))
      (node (ref "R30") (pin "2") (pinfunction "2_2") (pintype "passive"))
    )
    (net (code "44") (name "Net-(C15-Pad1)") (class "Default")
      (node (ref "C15") (pin "1") (pinfunction "1_1") (pintype "passive"))
      (node (ref "R3") (pin "1") (pinfunction "1_1") (pintype "passive"))
      (node (ref "R4") (pin "1") (pinfunction "1_1") (pintype "passive"))
    )
    (net (code "45") (name "Net-(R2-Pad1)") (class "Default")
      (node (ref "R2") (pin "1") (pinfunction "1_1") (pintype "passive"))
      (node (ref "TX2") (pin "A") (pinfunction "A_A") (pintype "passive"))
    )
    (net (code "46") (name "Net-(R6-Pad1)") (class "Default")
      (node (ref "R6") (pin "1") (pinfunction "1_1") (pintype "passive"))
      (node (ref "VOUT1") (pin "A") (pinfunction "A_A") (pintype "passive"))
    )
    (net (code "47") (name "Net-(R12-Pad1)") (class "Default")
      (node (ref "R12") (pin "1") (pinfunction "1_1") (pintype "passive"))
      (node (ref "RX2") (pin "A") (pinfunction "A_A") (pintype "passive"))
    )
    (net (code "48") (name "Net-(R31-Pad1)") (class "Default")
      (node (ref "R31") (pin "1") (pinfunction "1_1") (pintype "passive"))
      (node (ref "RX3") (pin "A") (pinfunction "A_A") (pintype "passive"))
    )
    (net (code "49") (name "Net-(R32-Pad1)") (class "Default")
      (node (ref "R32") (pin "1") (pinfunction "1_1") (pintype "passive"))
      (node (ref "TX3") (pin "A") (pinfunction "A_A") (pintype "passive"))
    )
    (net (code "50") (name "Net-(S2-2)") (class "Default")
      (node (ref "R1") (pin "2") (pinfunction "2_2") (pintype "passive"))
      (node (ref "S2") (pin "B2") (pinfunction "2_B2") (pintype "passive"))
    )
    (net (code "51") (name "Net-(U$3-SW)") (class "Default")
      (node (ref "D5") (pin "C") (pinfunction "C_C") (pintype "passive"))
      (node (ref "L1") (pin "1") (pinfunction "1_1") (pintype "passive"))
      (node (ref "U$3") (pin "2") (pinfunction "SW_2") (pintype "bidirectional"))
    )
    (net (code "52") (name "Net-(U3-RB5)") (class "Default")
      (node (ref "J1") (pin "4") (pinfunction "4_4") (pintype "passive"))
      (node (ref "U3") (pin "41") (pinfunction "RB5_41") (pintype "bidirectional"))
    )
    (net (code "53") (name "Net-(U3-RB6)") (class "Default")
      (node (ref "J1") (pin "5") (pinfunction "5_5") (pintype "passive"))
      (node (ref "U3") (pin "42") (pinfunction "RB6_42") (pintype "bidirectional"))
    )
    (net (code "54") (name "Net-(U3-VCAP)") (class "Default")
      (node (ref "C4") (pin "1") (pinfunction "1_1") (pintype "passive"))
      (node (ref "U3") (pin "7") (pinfunction "VCAP_7") (pintype "power_in"))
    )
    (net (code "55") (name "OSC1") (class "Default")
      (node (ref "C19") (pin "2") (pinfunction "2_2") (pintype "passive"))
      (node (ref "R21") (pin "1") (pinfunction "1_1") (pintype "passive"))
      (node (ref "U$1") (pin "3") (pinfunction "3_3") (pintype "bidirectional"))
      (node (ref "U3") (pin "30") (pinfunction "RA2/OSC1_30") (pintype "bidirectional"))
    )
    (net (code "56") (name "OSC2") (class "Default")
      (node (ref "C18") (pin "2") (pinfunction "2_2") (pintype "passive"))
      (node (ref "R21") (pin "2") (pinfunction "2_2") (pintype "passive"))
      (node (ref "U$1") (pin "1") (pinfunction "1_1") (pintype "bidirectional"))
      (node (ref "U3") (pin "31") (pinfunction "RA3/OSC2_31") (pintype "bidirectional"))
    )
    (net (code "57") (name "RST") (class "Default")
      (node (ref "J1") (pin "1") (pinfunction "1_1") (pintype "passive"))
      (node (ref "J3") (pin "P$26") (pinfunction "WATCH_2_B_P$26") (pintype "passive"))
      (node (ref "R1") (pin "1") (pinfunction "1_1") (pintype "passive"))
      (node (ref "R3") (pin "2") (pinfunction "2_2") (pintype "passive"))
      (node (ref "U3") (pin "18") (pinfunction "MCLR_18") (pintype "bidirectional"))
    )
    (net (code "58") (name "RX_1") (class "Default")
      (node (ref "J7") (pin "1") (pinfunction "1_1") (pintype "passive"))
      (node (ref "RX2") (pin "C") (pinfunction "C_C") (pintype "passive"))
      (node (ref "U2") (pin "4") (pinfunction "RXD_4") (pintype "bidirectional"))
      (node (ref "U3") (pin "44") (pinfunction "RB8_44") (pintype "bidirectional"))
    )
    (net (code "59") (name "RX_2") (class "Default")
      (node (ref "J8") (pin "1") (pinfunction "1_1") (pintype "passive"))
      (node (ref "RX3") (pin "C") (pinfunction "C_C") (pintype "passive"))
      (node (ref "U3") (pin "34") (pinfunction "RA4/SDO1_34") (pintype "bidirectional"))
      (node (ref "U5") (pin "4") (pinfunction "RXD_4") (pintype "bidirectional"))
    )
    (net (code "60") (name "STBY-1") (class "Default")
      (node (ref "R14") (pin "2") (pinfunction "2_2") (pintype "passive"))
      (node (ref "U2") (pin "8") (pinfunction "STBY_8") (pintype "bidirectional"))
    )
    (net (code "61") (name "STBY-2") (class "Default")
      (node (ref "R16") (pin "2") (pinfunction "2_2") (pintype "passive"))
      (node (ref "U5") (pin "8") (pinfunction "STBY_8") (pintype "bidirectional"))
    )
    (net (code "62") (name "TX_1") (class "Default")
      (node (ref "J7") (pin "2") (pinfunction "2_2") (pintype "passive"))
      (node (ref "TX2") (pin "C") (pinfunction "C_C") (pintype "passive"))
      (node (ref "U2") (pin "1") (pinfunction "TXD_1") (pintype "bidirectional"))
      (node (ref "U3") (pin "43") (pinfunction "RB7_43") (pintype "bidirectional"))
    )
    (net (code "63") (name "TX_2") (class "Default")
      (node (ref "J8") (pin "2") (pinfunction "2_2") (pintype "passive"))
      (node (ref "TX3") (pin "C") (pinfunction "C_C") (pintype "passive"))
      (node (ref "U3") (pin "33") (pinfunction "RB4/SCL2_33") (pintype "bidirectional"))
      (node (ref "U5") (pin "1") (pinfunction "TXD_1") (pintype "bidirectional"))
    )
    (net (code "64") (name "WATCH_2") (class "Default")
      (node (ref "J3") (pin "P$19") (pinfunction "WATCH_2_P$19") (pintype "passive"))
      (node (ref "U3") (pin "21") (pinfunction "RB0/SS1_21") (pintype "bidirectional"))
    )
    (net (code "65") (name "unconnected-(J3-A9-PadP$9)") (class "Default")
      (node (ref "J3") (pin "P$9") (pinfunction "A9_P$9") (pintype "passive"))
    )
    (net (code "66") (name "unconnected-(J3-A10-PadP$10)") (class "Default")
      (node (ref "J3") (pin "P$10") (pinfunction "A10_P$10") (pintype "passive"))
    )
    (net (code "67") (name "unconnected-(J3-A11-PadP$11)") (class "Default")
      (node (ref "J3") (pin "P$11") (pinfunction "A11_P$11") (pintype "passive"))
    )
    (net (code "68") (name "unconnected-(J3-A32-PadP$32)") (class "Default")
      (node (ref "J3") (pin "P$32") (pinfunction "A32_P$32") (pintype "passive"))
    )
    (net (code "69") (name "unconnected-(J3-B2-PadP$34)") (class "Default")
      (node (ref "J3") (pin "P$34") (pinfunction "B2_P$34") (pintype "passive"))
    )
    (net (code "70") (name "unconnected-(J3-B3-PadP$35)") (class "Default")
      (node (ref "J3") (pin "P$35") (pinfunction "B3_P$35") (pintype "passive"))
    )
    (net (code "71") (name "unconnected-(J3-B4-PadP$36)") (class "Default")
      (node (ref "J3") (pin "P$36") (pinfunction "B4_P$36") (pintype "passive"))
    )
    (net (code "72") (name "unconnected-(J3-B5-PadP$37)") (class "Default")
      (node (ref "J3") (pin "P$37") (pinfunction "B5_P$37") (pintype "passive"))
    )
    (net (code "73") (name "unconnected-(J3-B6-PadP$38)") (class "Default")
      (node (ref "J3") (pin "P$38") (pinfunction "B6_P$38") (pintype "passive"))
    )
    (net (code "74") (name "unconnected-(J3-B7-PadP$39)") (class "Default")
      (node (ref "J3") (pin "P$39") (pinfunction "B7_P$39") (pintype "passive"))
    )
    (net (code "75") (name "unconnected-(J3-B8-PadP$40)") (class "Default")
      (node (ref "J3") (pin "P$40") (pinfunction "B8_P$40") (pintype "passive"))
    )
    (net (code "76") (name "unconnected-(J3-B9-PadP$41)") (class "Default")
      (node (ref "J3") (pin "P$41") (pinfunction "B9_P$41") (pintype "passive"))
    )
    (net (code "77") (name "unconnected-(J3-B10-PadP$42)") (class "Default")
      (node (ref "J3") (pin "P$42") (pinfunction "B10_P$42") (pintype "passive"))
    )
    (net (code "78") (name "unconnected-(J3-B11-PadP$43)") (class "Default")
      (node (ref "J3") (pin "P$43") (pinfunction "B11_P$43") (pintype "passive"))
    )
    (net (code "79") (name "unconnected-(J3-B12-PadP$44)") (class "Default")
      (node (ref "J3") (pin "P$44") (pinfunction "B12_P$44") (pintype "passive"))
    )
    (net (code "80") (name "unconnected-(J3-B13-PadP$45)") (class "Default")
      (node (ref "J3") (pin "P$45") (pinfunction "B13_P$45") (pintype "passive"))
    )
    (net (code "81") (name "unconnected-(J3-B14-PadP$46)") (class "Default")
      (node (ref "J3") (pin "P$46") (pinfunction "B14_P$46") (pintype "passive"))
    )
    (net (code "82") (name "unconnected-(J3-B15-PadP$47)") (class "Default")
      (node (ref "J3") (pin "P$47") (pinfunction "B15_P$47") (pintype "passive"))
    )
    (net (code "83") (name "unconnected-(J3-B16-PadP$48)") (class "Default")
      (node (ref "J3") (pin "P$48") (pinfunction "B16_P$48") (pintype "passive"))
    )
    (net (code "84") (name "unconnected-(J3-B17-PadP$49)") (class "Default")
      (node (ref "J3") (pin "P$49") (pinfunction "B17_P$49") (pintype "passive"))
    )
    (net (code "85") (name "unconnected-(J3-B18-PadP$50)") (class "Default")
      (node (ref "J3") (pin "P$50") (pinfunction "B18_P$50") (pintype "passive"))
    )
    (net (code "86") (name "unconnected-(J3-B19-PadP$51)") (class "Default")
      (node (ref "J3") (pin "P$51") (pinfunction "B19_P$51") (pintype "passive"))
    )
    (net (code "87") (name "unconnected-(J3-B20-PadP$52)") (class "Default")
      (node (ref "J3") (pin "P$52") (pinfunction "B20_P$52") (pintype "passive"))
    )
    (net (code "88") (name "unconnected-(J3-B21-PadP$53)") (class "Default")
      (node (ref "J3") (pin "P$53") (pinfunction "B21_P$53") (pintype "passive"))
    )
    (net (code "89") (name "unconnected-(J3-B22-PadP$54)") (class "Default")
      (node (ref "J3") (pin "P$54") (pinfunction "B22_P$54") (pintype "passive"))
    )
    (net (code "90") (name "unconnected-(J3-B23-PadP$55)") (class "Default")
      (node (ref "J3") (pin "P$55") (pinfunction "B23_P$55") (pintype "passive"))
    )
    (net (code "91") (name "unconnected-(J3-B24-PadP$56)") (class "Default")
      (node (ref "J3") (pin "P$56") (pinfunction "B24_P$56") (pintype "passive"))
    )
    (net (code "92") (name "unconnected-(J3-B25-PadP$57)") (class "Default")
      (node (ref "J3") (pin "P$57") (pinfunction "B25_P$57") (pintype "passive"))
    )
    (net (code "93") (name "unconnected-(J3-B26-PadP$58)") (class "Default")
      (node (ref "J3") (pin "P$58") (pinfunction "B26_P$58") (pintype "passive"))
    )
    (net (code "94") (name "unconnected-(J3-B27-PadP$59)") (class "Default")
      (node (ref "J3") (pin "P$59") (pinfunction "B27_P$59") (pintype "passive"))
    )
    (net (code "95") (name "unconnected-(J3-B28-PadP$60)") (class "Default")
      (node (ref "J3") (pin "P$60") (pinfunction "B28_P$60") (pintype "passive"))
    )
    (net (code "96") (name "unconnected-(J3-B29-PadP$61)") (class "Default")
      (node (ref "J3") (pin "P$61") (pinfunction "B29_P$61") (pintype "passive"))
    )
    (net (code "97") (name "unconnected-(J3-B30-PadP$62)") (class "Default")
      (node (ref "J3") (pin "P$62") (pinfunction "B30_P$62") (pintype "passive"))
    )
    (net (code "98") (name "unconnected-(J3-B31-PadP$63)") (class "Default")
      (node (ref "J3") (pin "P$63") (pinfunction "B31_P$63") (pintype "passive"))
    )
    (net (code "99") (name "unconnected-(J3-B32-PadP$64)") (class "Default")
      (node (ref "J3") (pin "P$64") (pinfunction "B32_P$64") (pintype "passive"))
    )
    (net (code "100") (name "unconnected-(J3-RX_0-PadP$13)") (class "Default")
      (node (ref "J3") (pin "P$13") (pinfunction "RX_0_P$13") (pintype "passive"))
    )
    (net (code "101") (name "unconnected-(J3-RX_1-PadP$15)") (class "Default")
      (node (ref "J3") (pin "P$15") (pinfunction "RX_1_P$15") (pintype "passive"))
    )
    (net (code "102") (name "unconnected-(J3-RX_2-PadP$17)") (class "Default")
      (node (ref "J3") (pin "P$17") (pinfunction "RX_2_P$17") (pintype "passive"))
    )
    (net (code "103") (name "unconnected-(J3-TX_0-PadP$12)") (class "Default")
      (node (ref "J3") (pin "P$12") (pinfunction "TX_0_P$12") (pintype "passive"))
    )
    (net (code "104") (name "unconnected-(J3-TX_1-PadP$14)") (class "Default")
      (node (ref "J3") (pin "P$14") (pinfunction "TX_1_P$14") (pintype "passive"))
    )
    (net (code "105") (name "unconnected-(J3-TX_2-PadP$16)") (class "Default")
      (node (ref "J3") (pin "P$16") (pinfunction "TX_2_P$16") (pintype "passive"))
    )
    (net (code "106") (name "unconnected-(J3-WATCH_1-PadP$18)") (class "Default")
      (node (ref "J3") (pin "P$18") (pinfunction "WATCH_1_P$18") (pintype "passive"))
    )
    (net (code "107") (name "unconnected-(J3-WATCH_1_B-PadP$25)") (class "Default")
      (node (ref "J3") (pin "P$25") (pinfunction "WATCH_1_B_P$25") (pintype "passive"))
    )
    (net (code "108") (name "unconnected-(J3-WATCH_3-PadP$20)") (class "Default")
      (node (ref "J3") (pin "P$20") (pinfunction "WATCH_3_P$20") (pintype "passive"))
    )
    (net (code "109") (name "unconnected-(J3-WATCH_3_B-PadP$27)") (class "Default")
      (node (ref "J3") (pin "P$27") (pinfunction "WATCH_3_B_P$27") (pintype "passive"))
    )
    (net (code "110") (name "unconnected-(J3-WATCH_4-PadP$21)") (class "Default")
      (node (ref "J3") (pin "P$21") (pinfunction "WATCH_4_P$21") (pintype "passive"))
    )
    (net (code "111") (name "unconnected-(J3-WATCH_4_B-PadP$28)") (class "Default")
      (node (ref "J3") (pin "P$28") (pinfunction "WATCH_4_B_P$28") (pintype "passive"))
    )
    (net (code "112") (name "unconnected-(J3-WATCH_5-PadP$22)") (class "Default")
      (node (ref "J3") (pin "P$22") (pinfunction "WATCH_5_P$22") (pintype "passive"))
    )
    (net (code "113") (name "unconnected-(J3-WATCH_5_B-PadP$29)") (class "Default")
      (node (ref "J3") (pin "P$29") (pinfunction "WATCH_5_B_P$29") (pintype "passive"))
    )
    (net (code "114") (name "unconnected-(J3-WATCH_6-PadP$23)") (class "Default")
      (node (ref "J3") (pin "P$23") (pinfunction "WATCH_6_P$23") (pintype "passive"))
    )
    (net (code "115") (name "unconnected-(J3-WATCH_6_B-PadP$30)") (class "Default")
      (node (ref "J3") (pin "P$30") (pinfunction "WATCH_6_B_P$30") (pintype "passive"))
    )
    (net (code "116") (name "unconnected-(J3-WATCH_7-PadP$24)") (class "Default")
      (node (ref "J3") (pin "P$24") (pinfunction "WATCH_7_P$24") (pintype "passive"))
    )
    (net (code "117") (name "unconnected-(J3-WATCH_7_B-PadP$31)") (class "Default")
      (node (ref "J3") (pin "P$31") (pinfunction "WATCH_7_B_P$31") (pintype "passive"))
    )
    (net (code "118") (name "unconnected-(U3-RA0-Pad19)") (class "Default")
      (node (ref "U3") (pin "19") (pinfunction "RA0_19") (pintype "bidirectional"))
    )
    (net (code "119") (name "unconnected-(U3-RA1-Pad20)") (class "Default")
      (node (ref "U3") (pin "20") (pinfunction "RA1_20") (pintype "bidirectional"))
    )
    (net (code "120") (name "unconnected-(U3-RB1-Pad22)") (class "Default")
      (node (ref "U3") (pin "22") (pinfunction "RB1_22") (pintype "bidirectional"))
    )
    (net (code "121") (name "unconnected-(U3-RB2-Pad23)") (class "Default")
      (node (ref "U3") (pin "23") (pinfunction "RB2_23") (pintype "bidirectional"))
    )
    (net (code "122") (name "unconnected-(U3-RB3-Pad24)") (class "Default")
      (node (ref "U3") (pin "24") (pinfunction "RB3_24") (pintype "bidirectional"))
    )
    (net (code "123") (name "unconnected-(U3-RB9-Pad1)") (class "Default")
      (node (ref "U3") (pin "1") (pinfunction "RB9_1") (pintype "bidirectional"))
    )
    (net (code "124") (name "unconnected-(U3-RC0-Pad25)") (class "Default")
      (node (ref "U3") (pin "25") (pinfunction "RC0_25") (pintype "bidirectional"))
    )
    (net (code "125") (name "unconnected-(U3-RC1-Pad26)") (class "Default")
      (node (ref "U3") (pin "26") (pinfunction "RC1_26") (pintype "bidirectional"))
    )
    (net (code "126") (name "unconnected-(U3-RC8-Pad4)") (class "Default")
      (node (ref "U3") (pin "4") (pinfunction "RC8_4") (pintype "bidirectional"))
    )
    (net (code "127") (name "unconnected-(U3-RC9-Pad5)") (class "Default")
      (node (ref "U3") (pin "5") (pinfunction "RC9_5") (pintype "bidirectional"))
    )
  )
)
